# ProPrj_Loongson_Aquarii_v1_9.net
KiCad netlist of a schematic drawn in EasyEDA Pro
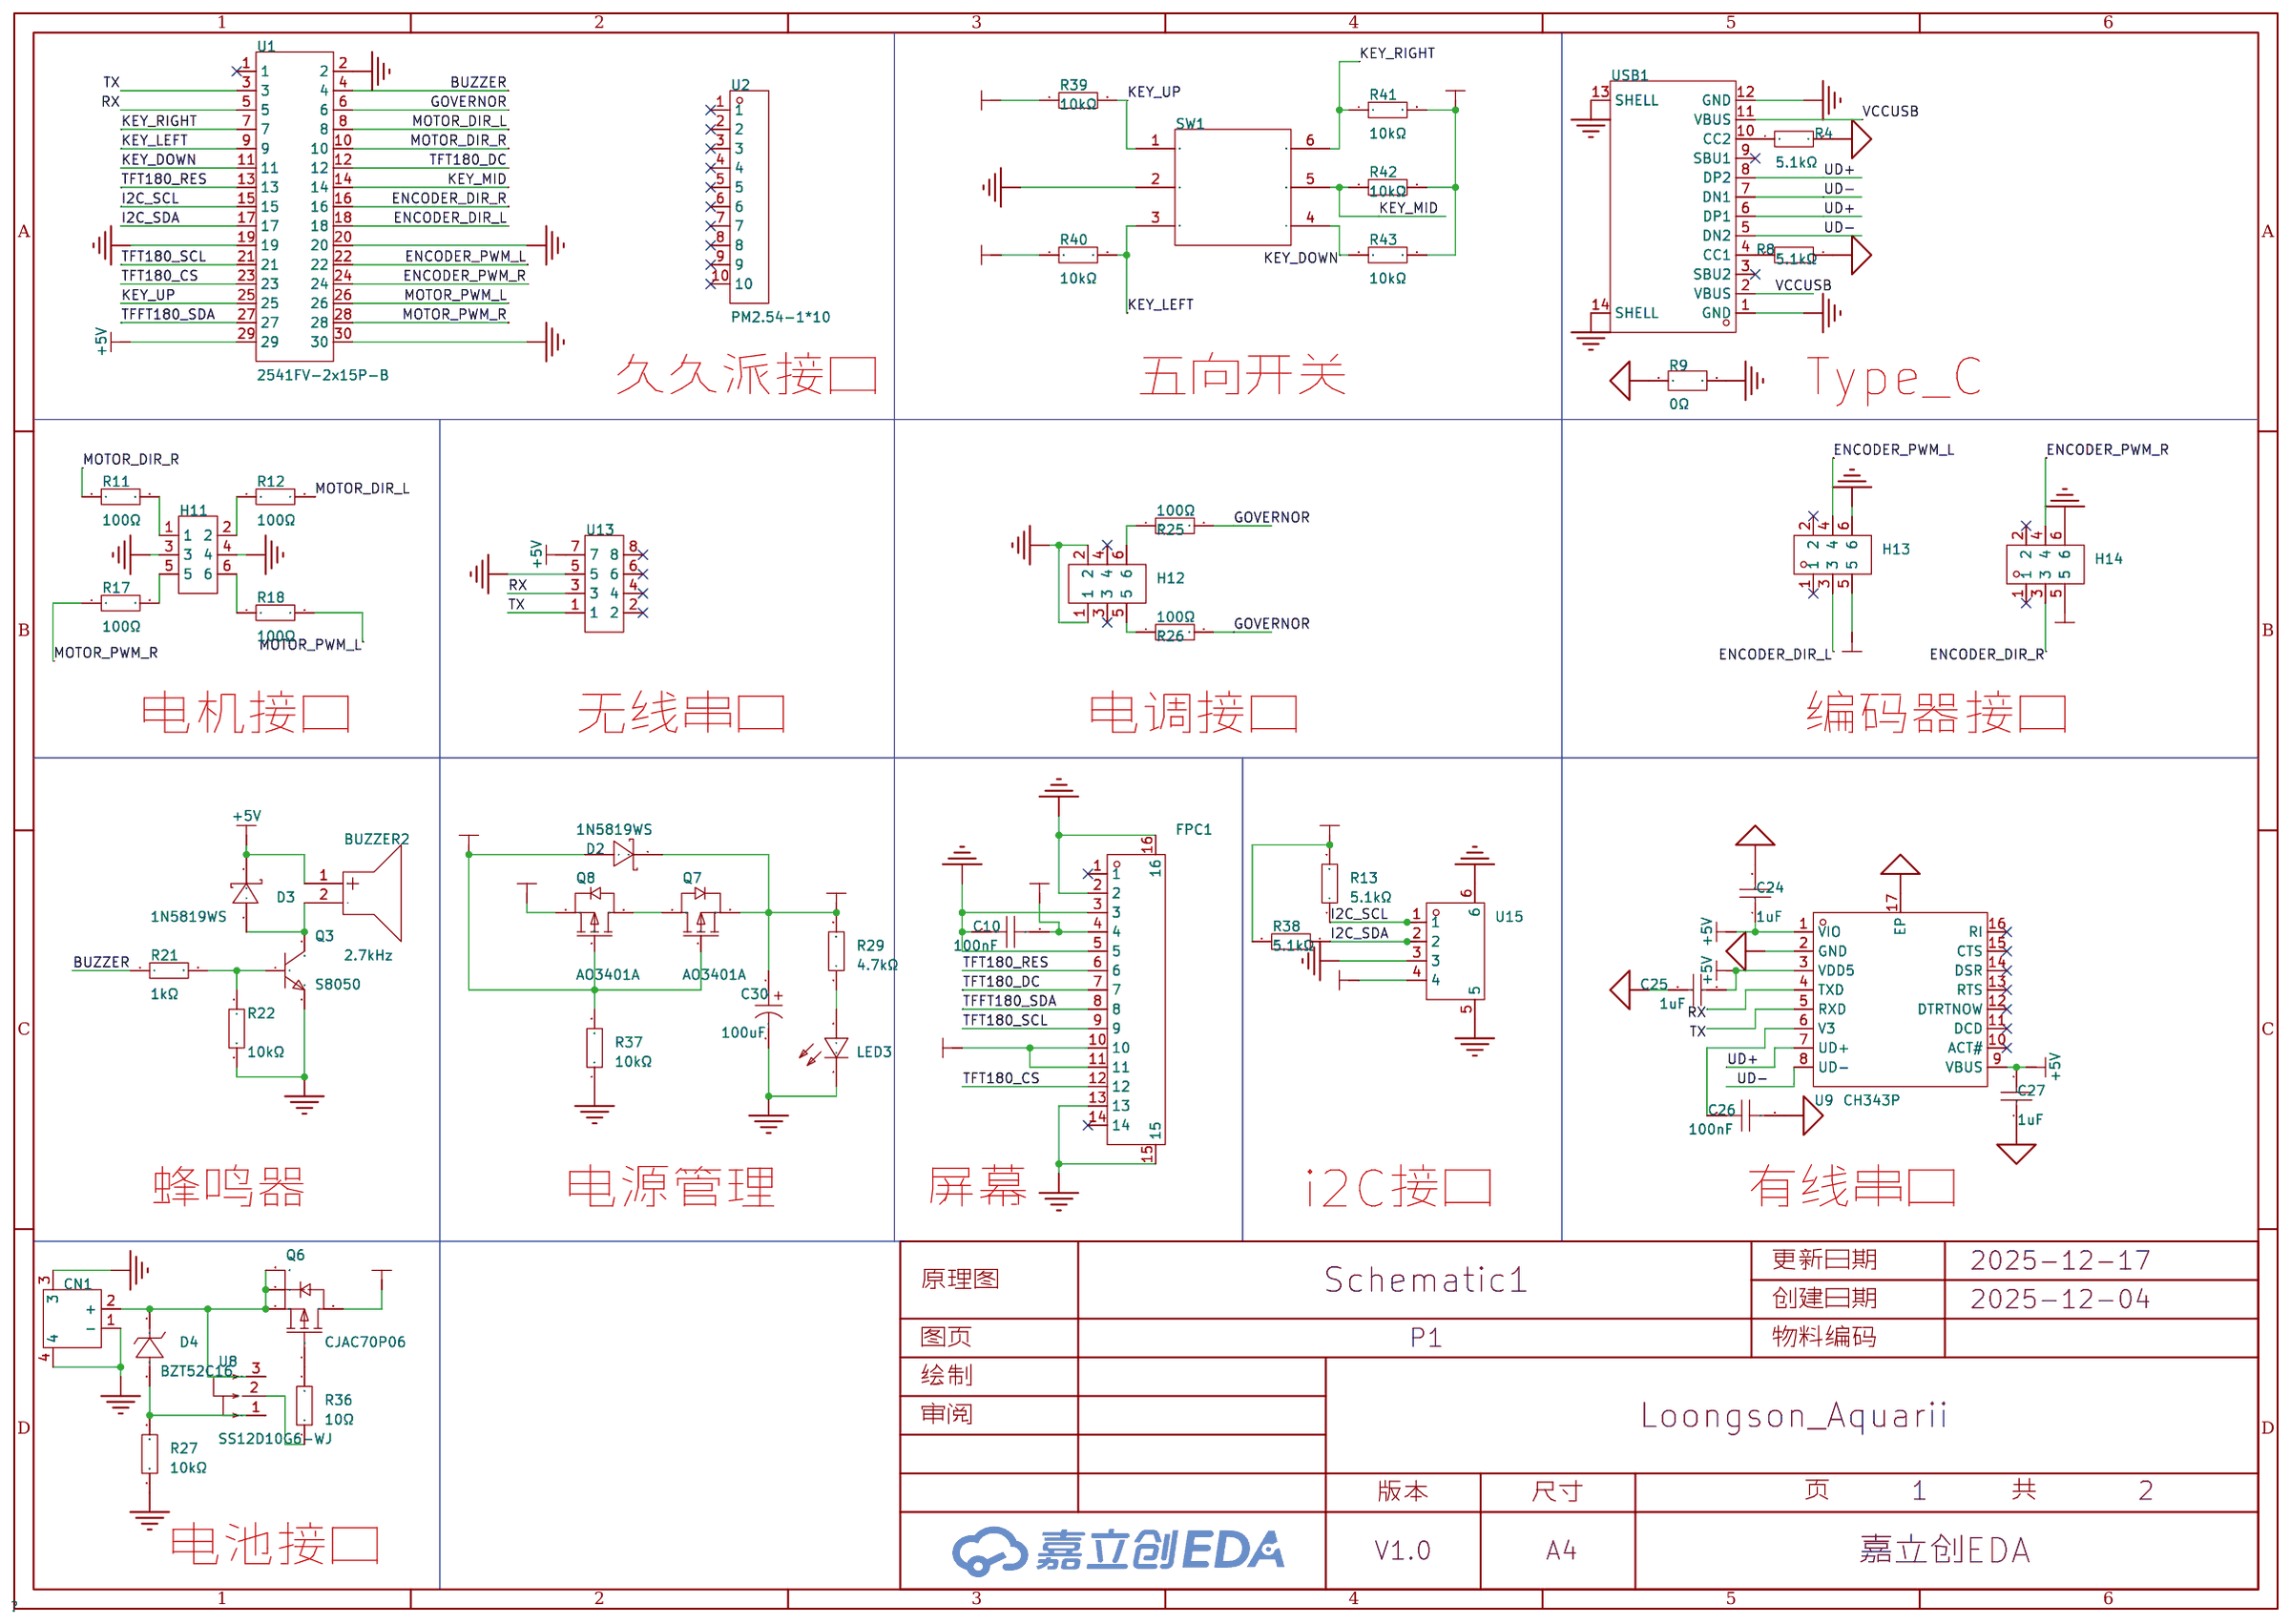
[diagram p0: P1]
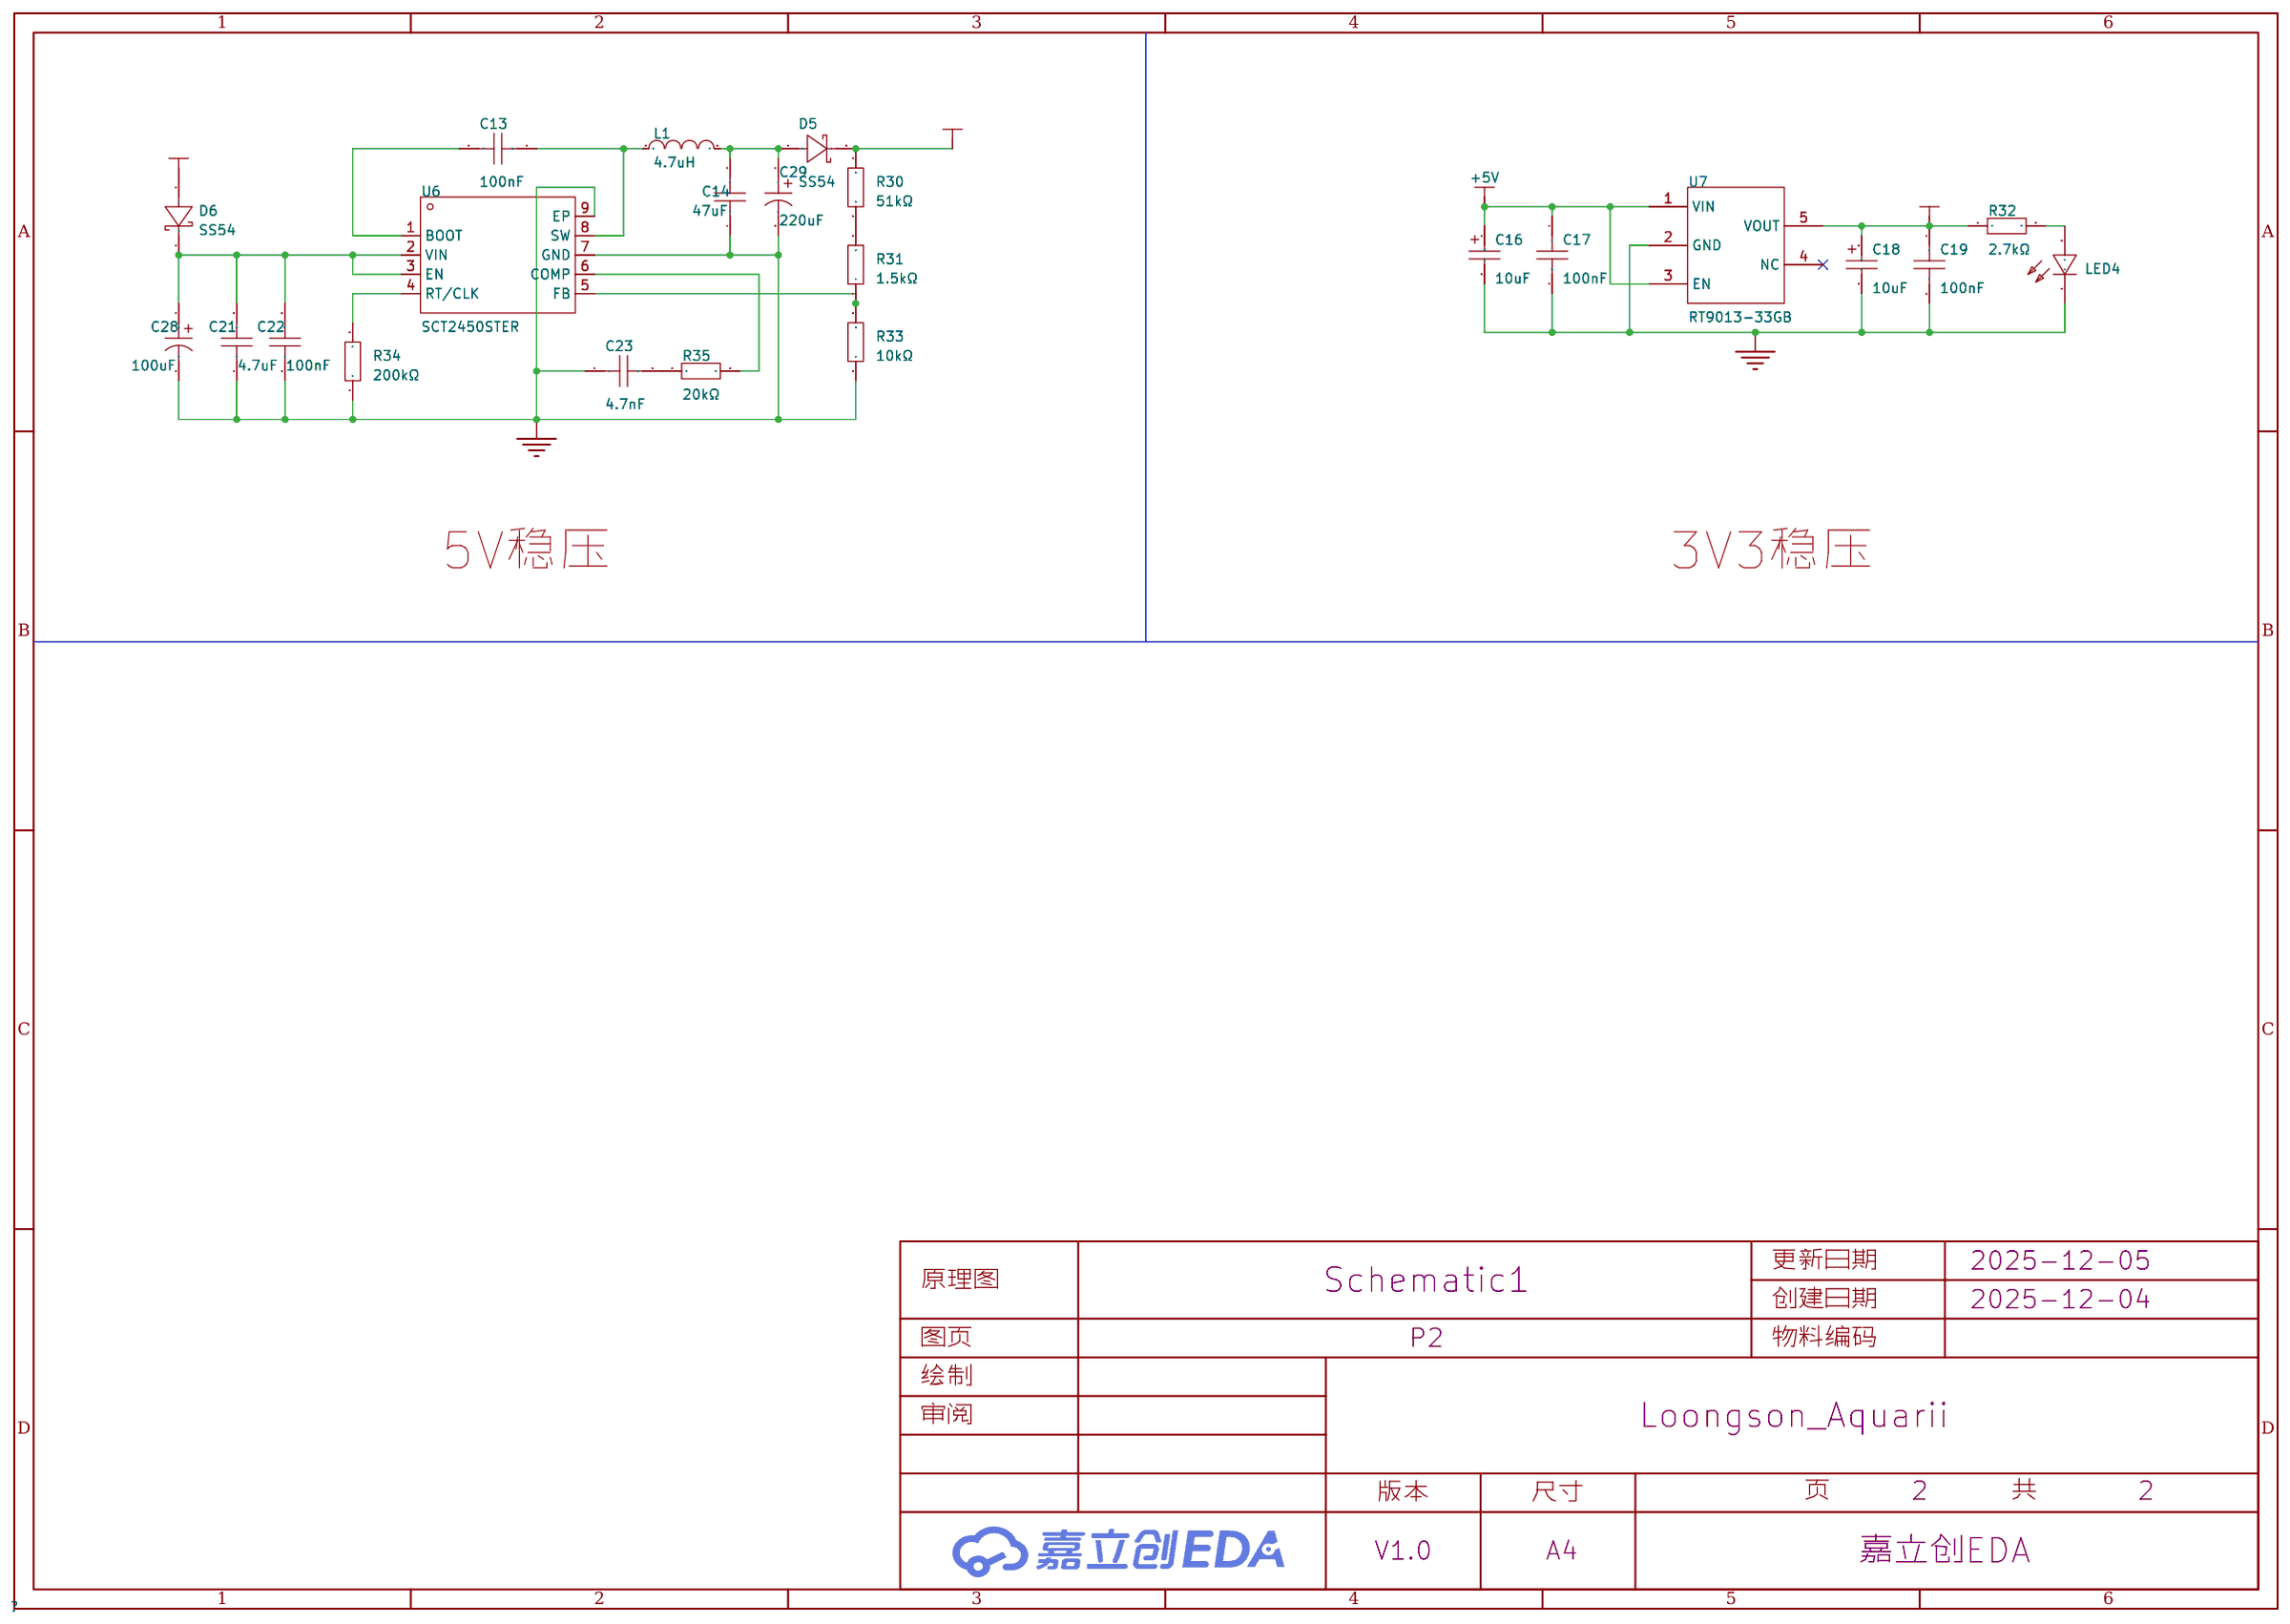
[diagram p1: P2]

(export (version "E")
  (design (tool "Eeschema 10.0.6"))
  (components
    (comp (ref "BUZZER2")
      (value "2.7kHz")
      (footprint "easyedapro:BUZ-SMD_GSC9032RB")
      (description "驱动方式:无源(外部驱动);构造类型:电磁式;额定电压:3.6V;频率:2.7kHz;声压(SPL):85dB;")
      (fields
        (field (name "Manufacturer Part") "GSC9032RB-16R2700")
        (field (name "Manufacturer") "INGHAi(赢海)")
      )
      (libsource (lib "easyedapro") (part "GSC9032RB-16R2700"))
    )
    (comp (ref "C10")
      (value "100nF")
      (footprint "easyedapro:C0603")
      (description "容值:100nF;精度:±10%;额定电压:50V;材质(温度系数):X7R;")
      (fields
        (field (name "Manufacturer Part") "CGA0603X7R104K500JT")
        (field (name "Manufacturer") "HRE(芯声)")
      )
      (libsource (lib "easyedapro") (part "CGA0603X7R104K500JT"))
    )
    (comp (ref "C24")
      (value "1uF")
      (footprint "easyedapro:C0805")
      (description "容值:1uF;精度:±10%;额定电压:50V;温度系数:X7R;")
      (fields
        (field (name "Manufacturer Part") "CL21B105KBFNNNE")
        (field (name "Manufacturer") "SAMSUNG(三星)")
      )
      (libsource (lib "easyedapro") (part "CL21B105KBFNNNE"))
    )
    (comp (ref "C25")
      (value "1uF")
      (footprint "easyedapro:C0805")
      (description "容值:1uF;精度:±10%;额定电压:50V;温度系数:X7R;")
      (fields
        (field (name "Manufacturer Part") "CL21B105KBFNNNE")
        (field (name "Manufacturer") "SAMSUNG(三星)")
      )
      (libsource (lib "easyedapro") (part "CL21B105KBFNNNE"))
    )
    (comp (ref "C26")
      (value "100nF")
      (footprint "easyedapro:C0603")
      (description "容值:100nF;精度:±10%;额定电压:50V;材质(温度系数):X7R;")
      (fields
        (field (name "Manufacturer Part") "CGA0603X7R104K500JT")
        (field (name "Manufacturer") "HRE(芯声)")
      )
      (libsource (lib "easyedapro") (part "CGA0603X7R104K500JT"))
    )
    (comp (ref "C27")
      (value "1uF")
      (footprint "easyedapro:C0805")
      (description "容值:1uF;精度:±10%;额定电压:50V;温度系数:X7R;")
      (fields
        (field (name "Manufacturer Part") "CL21B105KBFNNNE")
        (field (name "Manufacturer") "SAMSUNG(三星)")
      )
      (libsource (lib "easyedapro") (part "CL21B105KBFNNNE"))
    )
    (comp (ref "C30")
      (value "100uF")
      (footprint "easyedapro:CAP-SMD_BD6.3-L6.6-W6.6-FD-1")
      (description "容值:100uF;精度:±20%;额定电压:25V;纹波电流:72mA@120Hz;")
      (fields (field (name "Manufacturer Part") "JVJ25V100M6x5") (field (name "Manufacturer") "JIERR(捷而瑞)"))
      (libsource (lib "easyedapro") (part "JVJ25V100M6X5"))
    )
    (comp (ref "CN1")
      (value "XT30PW-M30.G.Y")
      (footprint "easyedapro:CONN-TH_XT30PW-M")
      (description "类别:-;类型1:-;")
      (fields (field (name "Manufacturer") "AMASS(艾迈斯)"))
      (libsource (lib "easyedapro") (part "XT30PW-M"))
    )
    (comp (ref "D2")
      (value "1N5819WS")
      (footprint "easyedapro:SOD-323_L1.8-W1.3-LS2.5-RD")
      (description "正向压降(Vf):600mV@1A;直流反向耐压(Vr):40V;整流电流:1A;")
      (fields (field (name "Manufacturer") "Hottech(合科泰)"))
      (libsource (lib "easyedapro") (part "1N5819WS"))
    )
    (comp (ref "D3")
      (value "1N5819WS")
      (footprint "easyedapro:SOD-323_L1.8-W1.3-LS2.5-RD")
      (description "正向压降(Vf):600mV@1A;直流反向耐压(Vr):40V;整流电流:1A;")
      (fields (field (name "Manufacturer") "Hottech(合科泰)"))
      (libsource (lib "easyedapro") (part "1N5819WS"))
    )
    (comp (ref "D4")
      (value "BZT52C16")
      (footprint "easyedapro:SOD-123_L2.7-W1.6-LS3.7-RD")
      (description "二极管配置:独立式;稳压值(标称值):16V;稳压值(范围):15.2V~16.8V;耗散功率(Pd):500mW;")
      (fields (field (name "Manufacturer") "宏嘉诚"))
      (libsource (lib "easyedapro") (part "BZT52C16_C19077413"))
    )
    (comp (ref "FPC1")
      (value "HC-FPC-05-09-14RLTAG")
      (footprint "easyedapro:FPC-SMD_14P-P0.50_HC-FPC-05-09-14RLTAG")
      (description "锁定特性:翻盖式;触点类型:双侧触点/上下接;触点数量:14P;间距:0.5mm;安装方式:卧贴;工作温度:-55°C~+85°C;")
      (fields (field (name "Manufacturer") "HCTL(华灿天禄)"))
      (libsource (lib "easyedapro") (part "HC-FPC-05-09-14RLTAG"))
    )
    (comp (ref "H11")
      (value "HX PZ2.54-2x3P TP")
      (footprint "easyedapro:HDR-SMD_6P-P2.54-V-M-R2-C3-LS7.2_M20-8760342")
      (fields (field (name "Manufacturer") "hanxia(韩下)"))
      (libsource (lib "easyedapro") (part "HX PZ2.54-2X3P TP"))
    )
    (comp (ref "H12")
      (value "HX PZ2.54-2x3P TP")
      (footprint "easyedapro:HDR-SMD_6P-P2.54-V-M-R2-C3-LS7.2_M20-8760342")
      (fields (field (name "Manufacturer") "hanxia(韩下)"))
      (libsource (lib "easyedapro") (part "HX PZ2.54-2X3P TP"))
    )
    (comp (ref "H13")
      (value "PZ254V-12-6P")
      (footprint "easyedapro:HDR-TH_6P-P2.54-V-M-R2-C3-S2.54")
      (fields (field (name "Manufacturer") "XFCN(兴飞)"))
      (libsource (lib "easyedapro") (part "PZ254V-12-6P"))
    )
    (comp (ref "H14")
      (value "PZ254V-12-6P")
      (footprint "easyedapro:HDR-TH_6P-P2.54-V-M-R2-C3-S2.54")
      (fields (field (name "Manufacturer") "XFCN(兴飞)"))
      (libsource (lib "easyedapro") (part "PZ254V-12-6P"))
    )
    (comp (ref "LED3")
      (value "NCD0603R1")
      (footprint "easyedapro:LED0603-RD_RED")
      (fields (field (name "Manufacturer") "国星光电"))
      (libsource (lib "easyedapro") (part "FC-DA1608HRK-620D"))
    )
    (comp (ref "Q3")
      (value "S8050")
      (footprint "easyedapro:SOT-23-3_L2.9-W1.6-P1.90-LS2.8-BR")
      (description "晶体管类型:NPN;集电极电流(Ic):500mA;集射极击穿电压(Vceo):25V;功率(Pd):300mW;")
      (fields (field (name "Manufacturer") "Hottech(合科泰)"))
      (libsource (lib "easyedapro") (part "S8050_C181158"))
    )
    (comp (ref "Q6")
      (value "CJAC70P06")
      (footprint "easyedapro:TDSON-8_L5.9-W5.2-P1.27-BL")
      (fields (field (name "Manufacturer") "CJ(江苏长电/长晶)"))
      (libsource (lib "easyedapro") (part "CJAC70P06"))
    )
    (comp (ref "Q7")
      (value "AO3401A")
      (footprint "easyedapro:SOT-23_L2.9-W1.3-P1.90-LS2.4-BR")
      (fields (field (name "Manufacturer") "UMW(友台半导体)"))
      (libsource (lib "easyedapro") (part "AO3401A_C347476"))
    )
    (comp (ref "Q8")
      (value "AO3401A")
      (footprint "easyedapro:SOT-23_L2.9-W1.3-P1.90-LS2.4-BR")
      (fields (field (name "Manufacturer") "UMW(友台半导体)"))
      (libsource (lib "easyedapro") (part "AO3401A_C347476"))
    )
    (comp (ref "R4")
      (value "5.1kΩ")
      (footprint "easyedapro:R0603")
      (description "电阻类型:厚膜电阻;阻值:5.1kΩ;精度:±1%;功率:100mW;最大工作电压:75V;温度系数:±100ppm/°C;")
      (fields
        (field (name "Manufacturer Part") "0603WAF5101T5E")
        (field (name "Manufacturer") "UNI-ROYAL(厚声)")
      )
      (libsource (lib "easyedapro") (part "0603WAF5101T5E"))
    )
    (comp (ref "R8")
      (value "5.1kΩ")
      (footprint "easyedapro:R0603")
      (description "电阻类型:厚膜电阻;阻值:5.1kΩ;精度:±1%;功率:100mW;最大工作电压:75V;温度系数:±100ppm/°C;")
      (fields
        (field (name "Manufacturer Part") "0603WAF5101T5E")
        (field (name "Manufacturer") "UNI-ROYAL(厚声)")
      )
      (libsource (lib "easyedapro") (part "0603WAF5101T5E"))
    )
    (comp (ref "R9")
      (value "0Ω")
      (footprint "easyedapro:R1206")
      (description "电阻类型:厚膜电阻;阻值:0Ω;精度:±5%;功率:250mW;最大工作电压:200V;")
      (fields (field (name "Manufacturer Part") "FRC1206P000 TS") (field (name "Manufacturer") "FOJAN(富捷)"))
      (libsource (lib "easyedapro") (part "FRC1206P000 TS"))
    )
    (comp (ref "R11")
      (value "100Ω")
      (footprint "easyedapro:R0603")
      (description "电阻类型:厚膜电阻;阻值:100Ω;精度:±1%;功率:100mW;最大工作电压:75V;温度系数:±200ppm/°C;")
      (fields
        (field (name "Manufacturer Part") "0603WAF1000T5E")
        (field (name "Manufacturer") "UNI-ROYAL(厚声)")
      )
      (libsource (lib "easyedapro") (part "0603WAF1000T5E"))
    )
    (comp (ref "R12")
      (value "100Ω")
      (footprint "easyedapro:R0603")
      (description "电阻类型:厚膜电阻;阻值:100Ω;精度:±1%;功率:100mW;最大工作电压:75V;温度系数:±200ppm/°C;")
      (fields
        (field (name "Manufacturer Part") "0603WAF1000T5E")
        (field (name "Manufacturer") "UNI-ROYAL(厚声)")
      )
      (libsource (lib "easyedapro") (part "0603WAF1000T5E"))
    )
    (comp (ref "R13")
      (value "5.1kΩ")
      (footprint "easyedapro:R0603")
      (description "电阻类型:厚膜电阻;阻值:5.1kΩ;精度:±1%;功率:100mW;最大工作电压:75V;温度系数:±100ppm/°C;")
      (fields
        (field (name "Manufacturer Part") "0603WAF5101T5E")
        (field (name "Manufacturer") "UNI-ROYAL(厚声)")
      )
      (libsource (lib "easyedapro") (part "0603WAF5101T5E"))
    )
    (comp (ref "R17")
      (value "100Ω")
      (footprint "easyedapro:R0603")
      (description "电阻类型:厚膜电阻;阻值:100Ω;精度:±1%;功率:100mW;最大工作电压:75V;温度系数:±200ppm/°C;")
      (fields
        (field (name "Manufacturer Part") "0603WAF1000T5E")
        (field (name "Manufacturer") "UNI-ROYAL(厚声)")
      )
      (libsource (lib "easyedapro") (part "0603WAF1000T5E"))
    )
    (comp (ref "R18")
      (value "100Ω")
      (footprint "easyedapro:R0603")
      (description "电阻类型:厚膜电阻;阻值:100Ω;精度:±1%;功率:100mW;最大工作电压:75V;温度系数:±200ppm/°C;")
      (fields
        (field (name "Manufacturer Part") "0603WAF1000T5E")
        (field (name "Manufacturer") "UNI-ROYAL(厚声)")
      )
      (libsource (lib "easyedapro") (part "0603WAF1000T5E"))
    )
    (comp (ref "R21")
      (value "1kΩ")
      (footprint "easyedapro:R0603")
      (description "电阻类型:厚膜电阻;阻值:1kΩ;精度:±1%;功率:100mW;工作电压:75V;温度系数:±100ppm/°C;")
      (fields
        (field (name "Manufacturer Part") "0603WAF1001T5E")
        (field (name "Manufacturer") "UNI-ROYAL(厚声)")
      )
      (libsource (lib "easyedapro") (part "0603WAF1001T5E"))
    )
    (comp (ref "R22")
      (value "10kΩ")
      (footprint "easyedapro:R0603")
      (description "电阻类型:厚膜电阻;阻值:10kΩ;精度:±1%;功率:100mW;最大工作电压:75V;温度系数:±100ppm/°C;")
      (fields
        (field (name "Manufacturer Part") "0603WAF1002T5E")
        (field (name "Manufacturer") "UNI-ROYAL(厚声)")
      )
      (libsource (lib "easyedapro") (part "0603WAF1002T5E"))
    )
    (comp (ref "R25")
      (value "100Ω")
      (footprint "easyedapro:R0603")
      (description "电阻类型:厚膜电阻;阻值:100Ω;精度:±1%;功率:100mW;最大工作电压:75V;温度系数:±200ppm/°C;")
      (fields
        (field (name "Manufacturer Part") "0603WAF1000T5E")
        (field (name "Manufacturer") "UNI-ROYAL(厚声)")
      )
      (libsource (lib "easyedapro") (part "0603WAF1000T5E"))
    )
    (comp (ref "R26")
      (value "100Ω")
      (footprint "easyedapro:R0603")
      (description "电阻类型:厚膜电阻;阻值:100Ω;精度:±1%;功率:100mW;最大工作电压:75V;温度系数:±200ppm/°C;")
      (fields
        (field (name "Manufacturer Part") "0603WAF1000T5E")
        (field (name "Manufacturer") "UNI-ROYAL(厚声)")
      )
      (libsource (lib "easyedapro") (part "0603WAF1000T5E"))
    )
    (comp (ref "R27")
      (value "10kΩ")
      (footprint "easyedapro:R0603")
      (description "电阻类型:厚膜电阻;阻值:10kΩ;精度:±1%;功率:100mW;最大工作电压:75V;温度系数:±100ppm/°C;")
      (fields
        (field (name "Manufacturer Part") "0603WAF1002T5E")
        (field (name "Manufacturer") "UNI-ROYAL(厚声)")
      )
      (libsource (lib "easyedapro") (part "0603WAF1002T5E"))
    )
    (comp (ref "R29")
      (value "4.7kΩ")
      (footprint "easyedapro:R0603")
      (description "电阻类型:厚膜电阻;阻值:4.7kΩ;精度:±1%;功率:100mW;最大工作电压:75V;温度系数:±100ppm/°C;")
      (fields
        (field (name "Manufacturer Part") "0603WAF4701T5E")
        (field (name "Manufacturer") "UNI-ROYAL(厚声)")
      )
      (libsource (lib "easyedapro") (part "0603WAF4701T5E"))
    )
    (comp (ref "R36")
      (value "10Ω")
      (footprint "easyedapro:R0603")
      (description "电阻类型:厚膜电阻;阻值:10Ω;精度:±1%;功率:100mW;最大工作电压:75V;温度系数:±400ppm/°C;")
      (fields
        (field (name "Manufacturer Part") "0603WAF100JT5E")
        (field (name "Manufacturer") "UNI-ROYAL(厚声)")
      )
      (libsource (lib "easyedapro") (part "0603WAF100JT5E"))
    )
    (comp (ref "R37")
      (value "10kΩ")
      (footprint "easyedapro:R0603")
      (description "电阻类型:厚膜电阻;阻值:10kΩ;精度:±1%;功率:100mW;最大工作电压:75V;温度系数:±100ppm/°C;")
      (fields
        (field (name "Manufacturer Part") "0603WAF1002T5E")
        (field (name "Manufacturer") "UNI-ROYAL(厚声)")
      )
      (libsource (lib "easyedapro") (part "0603WAF1002T5E"))
    )
    (comp (ref "R38")
      (value "5.1kΩ")
      (footprint "easyedapro:R0603")
      (description "电阻类型:厚膜电阻;阻值:5.1kΩ;精度:±1%;功率:100mW;最大工作电压:75V;温度系数:±100ppm/°C;")
      (fields
        (field (name "Manufacturer Part") "0603WAF5101T5E")
        (field (name "Manufacturer") "UNI-ROYAL(厚声)")
      )
      (libsource (lib "easyedapro") (part "0603WAF5101T5E"))
    )
    (comp (ref "R39")
      (value "10kΩ")
      (footprint "easyedapro:R0603")
      (description "电阻类型:厚膜电阻;阻值:10kΩ;精度:±1%;功率:100mW;最大工作电压:75V;温度系数:±100ppm/°C;")
      (fields
        (field (name "Manufacturer Part") "0603WAF1002T5E")
        (field (name "Manufacturer") "UNI-ROYAL(厚声)")
      )
      (libsource (lib "easyedapro") (part "0603WAF1002T5E"))
    )
    (comp (ref "R40")
      (value "10kΩ")
      (footprint "easyedapro:R0603")
      (description "电阻类型:厚膜电阻;阻值:10kΩ;精度:±1%;功率:100mW;最大工作电压:75V;温度系数:±100ppm/°C;")
      (fields
        (field (name "Manufacturer Part") "0603WAF1002T5E")
        (field (name "Manufacturer") "UNI-ROYAL(厚声)")
      )
      (libsource (lib "easyedapro") (part "0603WAF1002T5E"))
    )
    (comp (ref "R41")
      (value "10kΩ")
      (footprint "easyedapro:R0603")
      (description "电阻类型:厚膜电阻;阻值:10kΩ;精度:±1%;功率:100mW;最大工作电压:75V;温度系数:±100ppm/°C;")
      (fields
        (field (name "Manufacturer Part") "0603WAF1002T5E")
        (field (name "Manufacturer") "UNI-ROYAL(厚声)")
      )
      (libsource (lib "easyedapro") (part "0603WAF1002T5E"))
    )
    (comp (ref "R42")
      (value "10kΩ")
      (footprint "easyedapro:R0603")
      (description "电阻类型:厚膜电阻;阻值:10kΩ;精度:±1%;功率:100mW;最大工作电压:75V;温度系数:±100ppm/°C;")
      (fields
        (field (name "Manufacturer Part") "0603WAF1002T5E")
        (field (name "Manufacturer") "UNI-ROYAL(厚声)")
      )
      (libsource (lib "easyedapro") (part "0603WAF1002T5E"))
    )
    (comp (ref "R43")
      (value "10kΩ")
      (footprint "easyedapro:R0603")
      (description "电阻类型:厚膜电阻;阻值:10kΩ;精度:±1%;功率:100mW;最大工作电压:75V;温度系数:±100ppm/°C;")
      (fields
        (field (name "Manufacturer Part") "0603WAF1002T5E")
        (field (name "Manufacturer") "UNI-ROYAL(厚声)")
      )
      (libsource (lib "easyedapro") (part "0603WAF1002T5E"))
    )
    (comp (ref "SW1")
      (value "7*7*5-6P-L WX")
      (footprint "easyedapro:SW-SMD_8P-L7.0-W7.0-P1.40-LS7.4-TL")
      (fields (field (name "Manufacturer") "SHOU HAN(首韩)"))
      (libsource (lib "easyedapro") (part "7*7*5-6P-L WX"))
    )
    (comp (ref "U1")
      (value "2541FV-2x15P-B")
      (footprint "easyedapro:HDR-TH_30P-P2.54-V-F-R2-C15-S2.54")
      (fields (field (name "Manufacturer") "HanElectricity(瀚源)"))
      (libsource (lib "easyedapro") (part "2541FV-2X15P-B"))
    )
    (comp (ref "U2")
      (value "PM2.54-1*10")
      (footprint "easyedapro:HDR-TH_10P-P2.54-V-F")
      (fields (field (name "Manufacturer") "ZHOURI(洲日)"))
      (libsource (lib "easyedapro") (part "PM2.54-1*10"))
    )
    (comp (ref "U8")
      (value "SS12D10G6-WJ")
      (footprint "easyedapro:SW-TH_3P-P4.80_HX-SS12D10G6-WJ")
      (description "电路结构:单刀双掷;安装方式:弯插;开关颜色:黑色;额定电流:2A;额定电压:125V;工作寿命:3千次;")
      (fields (field (name "Manufacturer") "SHOU HAN(首韩)"))
      (libsource (lib "easyedapro") (part "SS12D10G6-WJ"))
    )
    (comp (ref "U9")
      (value "CH343P")
      (footprint "easyedapro:TQFN-16_L3.0-W3.0-P0.50-BL-EP1.7")
      (description "应用功能:USB转UART;USB协议版本:USB 2.0;通道数:-;数据速率:6Mbps;")
      (fields (field (name "Manufacturer") "WCH(南京沁恒)"))
      (libsource (lib "easyedapro") (part "CH343P"))
    )
    (comp (ref "U13")
      (value "5BME8-08872-204-W0")
      (footprint "easyedapro:CONN-SMD_5BME8-08872-204-W0")
      (fields (field (name "Manufacturer") "SAMZO(三佐)"))
      (libsource (lib "easyedapro") (part "5BME8-08872-204-W0"))
    )
    (comp (ref "U15")
      (value "2.54-4PWTDK")
      (footprint "easyedapro:CONN-SMD_4P-P2.50_SHOU_2.54-4PWTDK")
      (fields (field (name "Manufacturer") "SHOU HAN(首韩)"))
      (libsource (lib "easyedapro") (part "2.54-4PWTDK"))
    )
    (comp (ref "USB1")
      (value "TYPE-C 16PIN 2MD(073)")
      (footprint "easyedapro:USB-C-SMD_TYPE-C-6PIN-2MD-073")
      (description "连接器类型:Type-C;标准:USB 3.1;公母:母;安装方式:卧贴;触点数量:16P;端口数量:1;额定电流 - 电源:5A;工作温度范围:-25°C~+85°C;")
      (fields (field (name "Manufacturer") "SHOU HAN(首韩)"))
      (libsource (lib "easyedapro") (part "TYPE-C 16PIN 2MD(073)"))
    )
    (comp (ref "C13")
      (value "100nF")
      (footprint "easyedapro:C0603")
      (description "容值:100nF;精度:±10%;额定电压:50V;材质(温度系数):X7R;")
      (fields
        (field (name "Manufacturer Part") "CGA0603X7R104K500JT")
        (field (name "Manufacturer") "HRE(芯声)")
      )
      (libsource (lib "easyedapro") (part "CGA0603X7R104K500JT"))
    )
    (comp (ref "C14")
      (value "47uF")
      (footprint "easyedapro:C1206")
      (description "容值:47uF;精度:±20%;额定电压:25V;材质(温度系数):X5R;")
      (fields
        (field (name "Manufacturer Part") "CGA1206X5R476M250NT")
        (field (name "Manufacturer") "HRE(芯声)")
      )
      (libsource (lib "easyedapro") (part "CGA1206X5R476M250NT"))
    )
    (comp (ref "C16")
      (value "10uF")
      (footprint "easyedapro:CAP-SMD_L3.2-W1.6-RD-C7171")
      (description "容值:10uF;精度:±10%;额定电压:16V;等效串联电阻:3Ω@100kHz;")
      (fields (field (name "Manufacturer Part") "TAJA106K016RNJ") (field (name "Manufacturer") "Kyocera AVX"))
      (libsource (lib "easyedapro") (part "TAJA106K016RNJ"))
    )
    (comp (ref "C17")
      (value "100nF")
      (footprint "easyedapro:C0603")
      (description "容值:100nF;精度:±10%;额定电压:50V;材质(温度系数):X7R;")
      (fields
        (field (name "Manufacturer Part") "CGA0603X7R104K500JT")
        (field (name "Manufacturer") "HRE(芯声)")
      )
      (libsource (lib "easyedapro") (part "CGA0603X7R104K500JT"))
    )
    (comp (ref "C18")
      (value "10uF")
      (footprint "easyedapro:CAP-SMD_L3.2-W1.6-RD-C7171")
      (description "容值:10uF;精度:±10%;额定电压:16V;等效串联电阻:3Ω@100kHz;")
      (fields (field (name "Manufacturer Part") "TAJA106K016RNJ") (field (name "Manufacturer") "Kyocera AVX"))
      (libsource (lib "easyedapro") (part "TAJA106K016RNJ"))
    )
    (comp (ref "C19")
      (value "100nF")
      (footprint "easyedapro:C0603")
      (description "容值:100nF;精度:±10%;额定电压:50V;材质(温度系数):X7R;")
      (fields
        (field (name "Manufacturer Part") "CGA0603X7R104K500JT")
        (field (name "Manufacturer") "HRE(芯声)")
      )
      (libsource (lib "easyedapro") (part "CGA0603X7R104K500JT"))
    )
    (comp (ref "C21")
      (value "4.7uF")
      (footprint "easyedapro:C1206")
      (description "容值:4.7uF;精度:±10%;额定电压:35V;材质(温度系数):X5R;")
      (fields
        (field (name "Manufacturer Part") "CGA1206X5R475K350NT")
        (field (name "Manufacturer") "HRE(芯声)")
      )
      (libsource (lib "easyedapro") (part "CGA1206X5R475K350NT"))
    )
    (comp (ref "C22")
      (value "100nF")
      (footprint "easyedapro:C0603")
      (description "容值:100nF;精度:±10%;额定电压:50V;材质(温度系数):X7R;")
      (fields
        (field (name "Manufacturer Part") "CGA0603X7R104K500JT")
        (field (name "Manufacturer") "HRE(芯声)")
      )
      (libsource (lib "easyedapro") (part "CGA0603X7R104K500JT"))
    )
    (comp (ref "C23")
      (value "4.7nF")
      (footprint "easyedapro:C0603")
      (description "容值:4.7nF;精度:±10%;额定电压:50V;材质(温度系数):X7R;")
      (fields
        (field (name "Manufacturer Part") "CGA0603X7R472K500JT")
        (field (name "Manufacturer") "HRE(芯声)")
      )
      (libsource (lib "easyedapro") (part "CGA0603X7R472K500JT"))
    )
    (comp (ref "C28")
      (value "100uF")
      (footprint "easyedapro:CAP-SMD_BD6.3-L6.6-W6.6-FD-1")
      (description "容值:100uF;精度:±20%;额定电压:25V;纹波电流:72mA@120Hz;")
      (fields (field (name "Manufacturer Part") "JVJ25V100M6x5") (field (name "Manufacturer") "JIERR(捷而瑞)"))
      (libsource (lib "easyedapro") (part "JVJ25V100M6X5"))
    )
    (comp (ref "C29")
      (value "220uF")
      (footprint "easyedapro:CAP-SMD_BD6.3-L6.6-W6.6-LS7.3-FD-H7.7")
      (description "容值:220uF;精度:±20%;额定电压:25V;纹波电流:120mA@120Hz;")
      (fields (field (name "Manufacturer Part") "JVJ25V220M6x8") (field (name "Manufacturer") "JIERR(捷而瑞)"))
      (libsource (lib "easyedapro") (part "JVJ25V220M6X8"))
    )
    (comp (ref "D5")
      (value "SS54")
      (footprint "easyedapro:SMA_L4.3-W2.6-LS5.0-FD")
      (description "二极管配置:独立式;正向压降(Vf):550mV@5.0A;直流反向耐压(Vr):40V;整流电流:5A;")
      (fields (field (name "Manufacturer") "宏迦橙"))
      (libsource (lib "easyedapro") (part "SS54_C7420369"))
    )
    (comp (ref "D6")
      (value "SS54")
      (footprint "easyedapro:SMA_L4.3-W2.6-LS5.0-FD")
      (description "二极管配置:独立式;正向压降(Vf):550mV@5.0A;直流反向耐压(Vr):40V;整流电流:5A;")
      (fields (field (name "Manufacturer") "宏迦橙"))
      (libsource (lib "easyedapro") (part "SS54_C7420369"))
    )
    (comp (ref "L1")
      (value "4.7uH")
      (footprint "easyedapro:IND-SMD_L5.4-W5.2_FXL0530")
      (description "电感值:4.7uH;精度:±20%;额定电流:4.5A;饱和电流(Isat):5A;类型:一体成型电感;")
      (fields (field (name "Manufacturer Part") "FXL0530-4R7-M") (field (name "Manufacturer") "cjiang(长江微电)"))
      (libsource (lib "easyedapro") (part "FXL0530-4R7-M"))
    )
    (comp (ref "LED4")
      (value "NCD0603R1")
      (footprint "easyedapro:LED0603-RD_RED")
      (fields (field (name "Manufacturer") "国星光电"))
      (libsource (lib "easyedapro") (part "FC-DA1608HRK-620D"))
    )
    (comp (ref "R30")
      (value "51kΩ")
      (footprint "easyedapro:R0603")
      (description "电阻类型:厚膜电阻;阻值:51kΩ;精度:±1%;功率:100mW;最大工作电压:75V;温度系数:±100ppm/°C;")
      (fields
        (field (name "Manufacturer Part") "0603WAF5102T5E")
        (field (name "Manufacturer") "UNI-ROYAL(厚声)")
      )
      (libsource (lib "easyedapro") (part "0603WAF5102T5E"))
    )
    (comp (ref "R31")
      (value "1.5kΩ")
      (footprint "easyedapro:R0603")
      (description "电阻类型:厚膜电阻;阻值:1.5kΩ;精度:±1%;功率:100mW;最大工作电压:75V;温度系数:±100ppm/°C;")
      (fields
        (field (name "Manufacturer Part") "0603WAF1501T5E")
        (field (name "Manufacturer") "UNI-ROYAL(厚声)")
      )
      (libsource (lib "easyedapro") (part "0603WAF1501T5E"))
    )
    (comp (ref "R32")
      (value "2.7kΩ")
      (footprint "easyedapro:R0603")
      (description "电阻类型:厚膜电阻;阻值:2.7kΩ;精度:±1%;功率:100mW;最大工作电压:75V;温度系数:±100ppm/°C;")
      (fields
        (field (name "Manufacturer Part") "0603WAF2701T5E")
        (field (name "Manufacturer") "UNI-ROYAL(厚声)")
      )
      (libsource (lib "easyedapro") (part "0603WAF2701T5E"))
    )
    (comp (ref "R33")
      (value "10kΩ")
      (footprint "easyedapro:R0603")
      (description "电阻类型:厚膜电阻;阻值:10kΩ;精度:±1%;功率:100mW;最大工作电压:75V;温度系数:±100ppm/°C;")
      (fields
        (field (name "Manufacturer Part") "0603WAF1002T5E")
        (field (name "Manufacturer") "UNI-ROYAL(厚声)")
      )
      (libsource (lib "easyedapro") (part "0603WAF1002T5E"))
    )
    (comp (ref "R34")
      (value "200kΩ")
      (footprint "easyedapro:R0603")
      (description "电阻类型:厚膜电阻;阻值:200kΩ;精度:±1%;功率:100mW;最大工作电压:75V;温度系数:±100ppm/°C;")
      (fields
        (field (name "Manufacturer Part") "0603WAF2003T5E")
        (field (name "Manufacturer") "UNI-ROYAL(厚声)")
      )
      (libsource (lib "easyedapro") (part "0603WAF2003T5E"))
    )
    (comp (ref "R35")
      (value "20kΩ")
      (footprint "easyedapro:R0603")
      (description "电阻类型:厚膜电阻;阻值:20kΩ;精度:±1%;功率:100mW;最大工作电压:75V;温度系数:±100ppm/°C;")
      (fields
        (field (name "Manufacturer Part") "0603WAF2002T5E")
        (field (name "Manufacturer") "UNI-ROYAL(厚声)")
      )
      (libsource (lib "easyedapro") (part "0603WAF2002T5E"))
    )
    (comp (ref "U6")
      (value "SCT2450STER")
      (footprint "easyedapro:ESOP-8_L4.9-W3.9-P1.27-LS6.0-BL-EP")
      (description "功能类型:降压型;工作电压:3.8V~36V;输出电流:5A;")
      (fields (field (name "Manufacturer") "SCT(芯洲科技)"))
      (libsource (lib "easyedapro") (part "SCT2450STER"))
    )
    (comp (ref "U7")
      (value "RT9013-33GB")
      (footprint "easyedapro:SOT-23-5_L3.0-W1.7-P0.95-LS2.8-BL")
      (description "输出类型:固定;最大输入电压:5.5V;输出电压:3.3V;输出电流:500mA;电源纹波抑制比(PSRR):50dB@(10kHz);输出极性:正极;")
      (fields (field (name "Manufacturer") "RICHTEK(立锜)"))
      (libsource (lib "easyedapro") (part "RT9013-33GB"))
    )
  )
  (nets
    (net (code "1") (name "+5V") (class "Default")
      (node (ref "BUZZER2") (pin "1") (pinfunction "+_1") (pintype "unspecified"))
      (node (ref "C16") (pin "1") (pinfunction "1_1") (pintype "input"))
      (node (ref "C17") (pin "1") (pinfunction "1_1") (pintype "unspecified"))
      (node (ref "C24") (pin "1") (pinfunction "1_1") (pintype "input"))
      (node (ref "C25") (pin "1") (pinfunction "1_1") (pintype "input"))
      (node (ref "C27") (pin "2") (pinfunction "2_2") (pintype "input"))
      (node (ref "C30") (pin "1") (pinfunction "1_1") (pintype "input"))
      (node (ref "D2") (pin "1") (pinfunction "K_1") (pintype "unspecified"))
      (node (ref "D3") (pin "1") (pinfunction "K_1") (pintype "unspecified"))
      (node (ref "Q7") (pin "2") (pinfunction "S_2") (pintype "unspecified"))
      (node (ref "R29") (pin "2") (pinfunction "2_2") (pintype "input"))
      (node (ref "U1") (pin "29") (pinfunction "29_29") (pintype "unspecified"))
      (node (ref "U13") (pin "7") (pinfunction "7_7") (pintype "unspecified"))
      (node (ref "U7") (pin "1") (pinfunction "VIN_1") (pintype "unspecified"))
      (node (ref "U7") (pin "3") (pinfunction "EN_3") (pintype "unspecified"))
      (node (ref "U9") (pin "1") (pinfunction "VIO_1") (pintype "unspecified"))
      (node (ref "U9") (pin "3") (pinfunction "VDD5_3") (pintype "unspecified"))
      (node (ref "U9") (pin "9") (pinfunction "VBUS_9") (pintype "unspecified"))
    )
    (net (code "2") (name "3V3") (class "Default")
      (node (ref "C10") (pin "2") (pinfunction "2_2") (pintype "unspecified"))
      (node (ref "C18") (pin "1") (pinfunction "1_1") (pintype "input"))
      (node (ref "C19") (pin "1") (pinfunction "1_1") (pintype "unspecified"))
      (node (ref "FPC1") (pin "10") (pinfunction "10_10") (pintype "unspecified"))
      (node (ref "FPC1") (pin "11") (pinfunction "11_11") (pintype "unspecified"))
      (node (ref "FPC1") (pin "4") (pinfunction "4_4") (pintype "unspecified"))
      (node (ref "H13") (pin "5") (pinfunction "5_5") (pintype "unspecified"))
      (node (ref "H14") (pin "5") (pinfunction "5_5") (pintype "unspecified"))
      (node (ref "R13") (pin "2") (pinfunction "2_2") (pintype "input"))
      (node (ref "R32") (pin "1") (pinfunction "1_1") (pintype "input"))
      (node (ref "R38") (pin "2") (pinfunction "2_2") (pintype "input"))
      (node (ref "R39") (pin "1") (pinfunction "1_1") (pintype "input"))
      (node (ref "R40") (pin "1") (pinfunction "1_1") (pintype "input"))
      (node (ref "R41") (pin "2") (pinfunction "2_2") (pintype "input"))
      (node (ref "R42") (pin "2") (pinfunction "2_2") (pintype "input"))
      (node (ref "R43") (pin "2") (pinfunction "2_2") (pintype "input"))
      (node (ref "U15") (pin "4") (pinfunction "4_4") (pintype "unspecified"))
      (node (ref "U7") (pin "5") (pinfunction "VOUT_5") (pintype "unspecified"))
    )
    (net (code "3") (name "AGND") (class "Default")
      (node (ref "C24") (pin "2") (pinfunction "2_2") (pintype "input"))
      (node (ref "C25") (pin "2") (pinfunction "2_2") (pintype "input"))
      (node (ref "C26") (pin "2") (pinfunction "2_2") (pintype "unspecified"))
      (node (ref "C27") (pin "1") (pinfunction "1_1") (pintype "input"))
      (node (ref "R4") (pin "2") (pinfunction "2_2") (pintype "input"))
      (node (ref "R8") (pin "2") (pinfunction "2_2") (pintype "input"))
      (node (ref "R9") (pin "1") (pinfunction "1_1") (pintype "unspecified"))
      (node (ref "U9") (pin "17") (pinfunction "EP_17") (pintype "unspecified"))
      (node (ref "U9") (pin "2") (pinfunction "GND_2") (pintype "unspecified"))
    )
    (net (code "4") (name "BUZZER") (class "Default")
      (node (ref "R21") (pin "1") (pinfunction "1_1") (pintype "input"))
      (node (ref "U1") (pin "4") (pinfunction "4_4") (pintype "unspecified"))
    )
    (net (code "5") (name "ENCODER_DIR_L") (class "Default")
      (node (ref "H13") (pin "3") (pinfunction "3_3") (pintype "unspecified"))
      (node (ref "U1") (pin "18") (pinfunction "18_18") (pintype "unspecified"))
    )
    (net (code "6") (name "ENCODER_DIR_R") (class "Default")
      (node (ref "H14") (pin "3") (pinfunction "3_3") (pintype "unspecified"))
      (node (ref "U1") (pin "16") (pinfunction "16_16") (pintype "unspecified"))
    )
    (net (code "7") (name "ENCODER_PWM_L") (class "Default")
      (node (ref "H13") (pin "4") (pinfunction "4_4") (pintype "unspecified"))
      (node (ref "U1") (pin "22") (pinfunction "22_22") (pintype "unspecified"))
    )
    (net (code "8") (name "ENCODER_PWM_R") (class "Default")
      (node (ref "H14") (pin "4") (pinfunction "4_4") (pintype "unspecified"))
      (node (ref "U1") (pin "24") (pinfunction "24_24") (pintype "unspecified"))
    )
    (net (code "9") (name "GND") (class "Default")
      (node (ref "C10") (pin "1") (pinfunction "1_1") (pintype "unspecified"))
      (node (ref "C14") (pin "1") (pinfunction "1_1") (pintype "unspecified"))
      (node (ref "C16") (pin "2") (pinfunction "2_2") (pintype "input"))
      (node (ref "C17") (pin "2") (pinfunction "2_2") (pintype "unspecified"))
      (node (ref "C18") (pin "2") (pinfunction "2_2") (pintype "input"))
      (node (ref "C19") (pin "2") (pinfunction "2_2") (pintype "unspecified"))
      (node (ref "C21") (pin "1") (pinfunction "1_1") (pintype "unspecified"))
      (node (ref "C22") (pin "1") (pinfunction "1_1") (pintype "unspecified"))
      (node (ref "C23") (pin "1") (pinfunction "1_1") (pintype "unspecified"))
      (node (ref "C28") (pin "2") (pinfunction "2_2") (pintype "input"))
      (node (ref "C29") (pin "2") (pinfunction "2_2") (pintype "input"))
      (node (ref "C30") (pin "2") (pinfunction "2_2") (pintype "input"))
      (node (ref "CN1") (pin "1") (pinfunction "-_1") (pintype "unspecified"))
      (node (ref "CN1") (pin "3") (pinfunction "3_3") (pintype "unspecified"))
      (node (ref "CN1") (pin "4") (pinfunction "4_4") (pintype "unspecified"))
      (node (ref "FPC1") (pin "13") (pinfunction "13_13") (pintype "unspecified"))
      (node (ref "FPC1") (pin "15") (pinfunction "15_15") (pintype "unspecified"))
      (node (ref "FPC1") (pin "16") (pinfunction "16_16") (pintype "unspecified"))
      (node (ref "FPC1") (pin "2") (pinfunction "2_2") (pintype "unspecified"))
      (node (ref "FPC1") (pin "3") (pinfunction "3_3") (pintype "unspecified"))
      (node (ref "FPC1") (pin "5") (pinfunction "5_5") (pintype "unspecified"))
      (node (ref "H11") (pin "3") (pinfunction "3_3") (pintype "unspecified"))
      (node (ref "H11") (pin "4") (pinfunction "4_4") (pintype "unspecified"))
      (node (ref "H12") (pin "1") (pinfunction "1_1") (pintype "unspecified"))
      (node (ref "H12") (pin "2") (pinfunction "2_2") (pintype "unspecified"))
      (node (ref "H13") (pin "6") (pinfunction "6_6") (pintype "unspecified"))
      (node (ref "H14") (pin "6") (pinfunction "6_6") (pintype "unspecified"))
      (node (ref "LED3") (pin "1") (pinfunction "K_1") (pintype "input"))
      (node (ref "LED4") (pin "1") (pinfunction "K_1") (pintype "input"))
      (node (ref "Q3") (pin "2") (pinfunction "2_2") (pintype "input"))
      (node (ref "R22") (pin "2") (pinfunction "2_2") (pintype "input"))
      (node (ref "R27") (pin "1") (pinfunction "1_1") (pintype "input"))
      (node (ref "R33") (pin "1") (pinfunction "1_1") (pintype "input"))
      (node (ref "R34") (pin "1") (pinfunction "1_1") (pintype "input"))
      (node (ref "R37") (pin "1") (pinfunction "1_1") (pintype "input"))
      (node (ref "R9") (pin "2") (pinfunction "2_2") (pintype "unspecified"))
      (node (ref "SW1") (pin "2") (pinfunction "2_2") (pintype "unspecified"))
      (node (ref "U1") (pin "19") (pinfunction "19_19") (pintype "unspecified"))
      (node (ref "U1") (pin "2") (pinfunction "2_2") (pintype "unspecified"))
      (node (ref "U1") (pin "20") (pinfunction "20_20") (pintype "unspecified"))
      (node (ref "U1") (pin "30") (pinfunction "30_30") (pintype "unspecified"))
      (node (ref "U13") (pin "5") (pinfunction "5_5") (pintype "unspecified"))
      (node (ref "U15") (pin "3") (pinfunction "3_3") (pintype "unspecified"))
      (node (ref "U15") (pin "5") (pinfunction "5_5") (pintype "unspecified"))
      (node (ref "U15") (pin "6") (pinfunction "6_6") (pintype "unspecified"))
      (node (ref "U6") (pin "7") (pinfunction "GND_7") (pintype "unspecified"))
      (node (ref "U6") (pin "9") (pinfunction "EP_9") (pintype "unspecified"))
      (node (ref "U7") (pin "2") (pinfunction "GND_2") (pintype "unspecified"))
      (node (ref "USB1") (pin "1") (pinfunction "GND_1") (pintype "unspecified"))
      (node (ref "USB1") (pin "12") (pinfunction "GND_12") (pintype "unspecified"))
      (node (ref "USB1") (pin "13") (pinfunction "SHELL_13") (pintype "unspecified"))
      (node (ref "USB1") (pin "14") (pinfunction "SHELL_14") (pintype "unspecified"))
    )
    (net (code "10") (name "GOVERNOR") (class "Default")
      (node (ref "R25") (pin "2") (pinfunction "2_2") (pintype "input"))
      (node (ref "R26") (pin "2") (pinfunction "2_2") (pintype "input"))
      (node (ref "U1") (pin "6") (pinfunction "6_6") (pintype "unspecified"))
    )
    (net (code "11") (name "I2C_SCL") (class "Default")
      (node (ref "R13") (pin "1") (pinfunction "1_1") (pintype "input"))
      (node (ref "U1") (pin "15") (pinfunction "15_15") (pintype "unspecified"))
      (node (ref "U15") (pin "1") (pinfunction "1_1") (pintype "unspecified"))
    )
    (net (code "12") (name "I2C_SDA") (class "Default")
      (node (ref "R38") (pin "1") (pinfunction "1_1") (pintype "input"))
      (node (ref "U1") (pin "17") (pinfunction "17_17") (pintype "unspecified"))
      (node (ref "U15") (pin "2") (pinfunction "2_2") (pintype "unspecified"))
    )
    (net (code "13") (name "KEY_DOWN") (class "Default")
      (node (ref "R43") (pin "1") (pinfunction "1_1") (pintype "input"))
      (node (ref "SW1") (pin "4") (pinfunction "4_4") (pintype "unspecified"))
      (node (ref "U1") (pin "11") (pinfunction "11_11") (pintype "unspecified"))
    )
    (net (code "14") (name "KEY_LEFT") (class "Default")
      (node (ref "R40") (pin "2") (pinfunction "2_2") (pintype "input"))
      (node (ref "SW1") (pin "3") (pinfunction "3_3") (pintype "unspecified"))
      (node (ref "U1") (pin "9") (pinfunction "9_9") (pintype "unspecified"))
    )
    (net (code "15") (name "KEY_MID") (class "Default")
      (node (ref "R42") (pin "1") (pinfunction "1_1") (pintype "input"))
      (node (ref "SW1") (pin "5") (pinfunction "5_5") (pintype "unspecified"))
      (node (ref "U1") (pin "14") (pinfunction "14_14") (pintype "unspecified"))
    )
    (net (code "16") (name "KEY_RIGHT") (class "Default")
      (node (ref "R41") (pin "1") (pinfunction "1_1") (pintype "input"))
      (node (ref "SW1") (pin "6") (pinfunction "6_6") (pintype "unspecified"))
      (node (ref "U1") (pin "7") (pinfunction "7_7") (pintype "unspecified"))
    )
    (net (code "17") (name "KEY_UP") (class "Default")
      (node (ref "R39") (pin "2") (pinfunction "2_2") (pintype "input"))
      (node (ref "SW1") (pin "1") (pinfunction "1_1") (pintype "unspecified"))
      (node (ref "U1") (pin "25") (pinfunction "25_25") (pintype "unspecified"))
    )
    (net (code "18") (name "MOTOR_DIR_L") (class "Default")
      (node (ref "R12") (pin "2") (pinfunction "2_2") (pintype "input"))
      (node (ref "U1") (pin "8") (pinfunction "8_8") (pintype "unspecified"))
    )
    (net (code "19") (name "MOTOR_DIR_R") (class "Default")
      (node (ref "R11") (pin "1") (pinfunction "1_1") (pintype "input"))
      (node (ref "U1") (pin "10") (pinfunction "10_10") (pintype "unspecified"))
    )
    (net (code "20") (name "MOTOR_PWM_L") (class "Default")
      (node (ref "R18") (pin "2") (pinfunction "2_2") (pintype "input"))
      (node (ref "U1") (pin "26") (pinfunction "26_26") (pintype "unspecified"))
    )
    (net (code "21") (name "MOTOR_PWM_R") (class "Default")
      (node (ref "R17") (pin "1") (pinfunction "1_1") (pintype "input"))
      (node (ref "U1") (pin "28") (pinfunction "28_28") (pintype "unspecified"))
    )
    (net (code "22") (name "Net-(BUZZER2--)") (class "Default")
      (node (ref "BUZZER2") (pin "2") (pinfunction "-_2") (pintype "unspecified"))
      (node (ref "D3") (pin "2") (pinfunction "A_2") (pintype "unspecified"))
      (node (ref "Q3") (pin "3") (pinfunction "3_3") (pintype "input"))
    )
    (net (code "23") (name "Net-(C23-Pad2)") (class "Default")
      (node (ref "C23") (pin "2") (pinfunction "2_2") (pintype "unspecified"))
      (node (ref "R35") (pin "1") (pinfunction "1_1") (pintype "input"))
    )
    (net (code "24") (name "Net-(CN1-+)") (class "Default")
      (node (ref "CN1") (pin "2") (pinfunction "+_2") (pintype "unspecified"))
      (node (ref "D4") (pin "1") (pinfunction "K_1") (pintype "unspecified"))
      (node (ref "Q6") (pin "1") (pinfunction "S_1") (pintype "unspecified"))
      (node (ref "Q6") (pin "2") (pinfunction "S_2") (pintype "unspecified"))
      (node (ref "Q6") (pin "3") (pinfunction "S_3") (pintype "unspecified"))
      (node (ref "U8") (pin "3") (pinfunction "3_3") (pintype "unspecified"))
    )
    (net (code "25") (name "Net-(D4-A)") (class "Default")
      (node (ref "D4") (pin "2") (pinfunction "A_2") (pintype "unspecified"))
      (node (ref "R27") (pin "2") (pinfunction "2_2") (pintype "input"))
      (node (ref "U8") (pin "1") (pinfunction "1_1") (pintype "unspecified"))
    )
    (net (code "26") (name "Net-(D5-A)") (class "Default")
      (node (ref "C14") (pin "2") (pinfunction "2_2") (pintype "unspecified"))
      (node (ref "C29") (pin "1") (pinfunction "1_1") (pintype "input"))
      (node (ref "D5") (pin "1") (pinfunction "A_1") (pintype "unspecified"))
      (node (ref "L1") (pin "2") (pinfunction "2_2") (pintype "unspecified"))
    )
    (net (code "27") (name "Net-(D6-K)") (class "Default")
      (node (ref "C21") (pin "2") (pinfunction "2_2") (pintype "unspecified"))
      (node (ref "C22") (pin "2") (pinfunction "2_2") (pintype "unspecified"))
      (node (ref "C28") (pin "1") (pinfunction "1_1") (pintype "input"))
      (node (ref "D6") (pin "2") (pinfunction "K_2") (pintype "unspecified"))
      (node (ref "U6") (pin "2") (pinfunction "VIN_2") (pintype "unspecified"))
      (node (ref "U6") (pin "3") (pinfunction "EN_3") (pintype "unspecified"))
    )
    (net (code "28") (name "Net-(H11-Pad1)") (class "Default")
      (node (ref "H11") (pin "1") (pinfunction "1_1") (pintype "unspecified"))
      (node (ref "R11") (pin "2") (pinfunction "2_2") (pintype "input"))
    )
    (net (code "29") (name "Net-(H11-Pad2)") (class "Default")
      (node (ref "H11") (pin "2") (pinfunction "2_2") (pintype "unspecified"))
      (node (ref "R12") (pin "1") (pinfunction "1_1") (pintype "input"))
    )
    (net (code "30") (name "Net-(H11-Pad5)") (class "Default")
      (node (ref "H11") (pin "5") (pinfunction "5_5") (pintype "unspecified"))
      (node (ref "R17") (pin "2") (pinfunction "2_2") (pintype "input"))
    )
    (net (code "31") (name "Net-(H11-Pad6)") (class "Default")
      (node (ref "H11") (pin "6") (pinfunction "6_6") (pintype "unspecified"))
      (node (ref "R18") (pin "1") (pinfunction "1_1") (pintype "input"))
    )
    (net (code "32") (name "Net-(H12-Pad5)") (class "Default")
      (node (ref "H12") (pin "5") (pinfunction "5_5") (pintype "unspecified"))
      (node (ref "R26") (pin "1") (pinfunction "1_1") (pintype "input"))
    )
    (net (code "33") (name "Net-(H12-Pad6)") (class "Default")
      (node (ref "H12") (pin "6") (pinfunction "6_6") (pintype "unspecified"))
      (node (ref "R25") (pin "1") (pinfunction "1_1") (pintype "input"))
    )
    (net (code "34") (name "Net-(LED3-A)") (class "Default")
      (node (ref "LED3") (pin "2") (pinfunction "A_2") (pintype "input"))
      (node (ref "R29") (pin "1") (pinfunction "1_1") (pintype "input"))
    )
    (net (code "35") (name "Net-(LED4-A)") (class "Default")
      (node (ref "LED4") (pin "2") (pinfunction "A_2") (pintype "input"))
      (node (ref "R32") (pin "2") (pinfunction "2_2") (pintype "input"))
    )
    (net (code "36") (name "Net-(Q3-Pad1)") (class "Default")
      (node (ref "Q3") (pin "1") (pinfunction "1_1") (pintype "input"))
      (node (ref "R21") (pin "2") (pinfunction "2_2") (pintype "input"))
      (node (ref "R22") (pin "1") (pinfunction "1_1") (pintype "input"))
    )
    (net (code "37") (name "Net-(Q6-G)") (class "Default")
      (node (ref "Q6") (pin "4") (pinfunction "G_4") (pintype "unspecified"))
      (node (ref "R36") (pin "2") (pinfunction "2_2") (pintype "input"))
    )
    (net (code "38") (name "Net-(Q7-D)") (class "Default")
      (node (ref "Q7") (pin "3") (pinfunction "D_3") (pintype "unspecified"))
      (node (ref "Q8") (pin "3") (pinfunction "D_3") (pintype "unspecified"))
    )
    (net (code "39") (name "Net-(R30-Pad1)") (class "Default")
      (node (ref "R30") (pin "1") (pinfunction "1_1") (pintype "input"))
      (node (ref "R31") (pin "2") (pinfunction "2_2") (pintype "input"))
    )
    (net (code "40") (name "Net-(R36-Pad1)") (class "Default")
      (node (ref "R36") (pin "1") (pinfunction "1_1") (pintype "input"))
      (node (ref "U8") (pin "2") (pinfunction "2_2") (pintype "unspecified"))
    )
    (net (code "41") (name "Net-(U6-BOOT)") (class "Default")
      (node (ref "C13") (pin "2") (pinfunction "2_2") (pintype "unspecified"))
      (node (ref "U6") (pin "1") (pinfunction "BOOT_1") (pintype "unspecified"))
    )
    (net (code "42") (name "Net-(U6-COMP)") (class "Default")
      (node (ref "R35") (pin "2") (pinfunction "2_2") (pintype "input"))
      (node (ref "U6") (pin "6") (pinfunction "COMP_6") (pintype "unspecified"))
    )
    (net (code "43") (name "Net-(U6-FB)") (class "Default")
      (node (ref "R31") (pin "1") (pinfunction "1_1") (pintype "input"))
      (node (ref "R33") (pin "2") (pinfunction "2_2") (pintype "input"))
      (node (ref "U6") (pin "5") (pinfunction "FB_5") (pintype "unspecified"))
    )
    (net (code "44") (name "Net-(U6-RT{slash}CLK)") (class "Default")
      (node (ref "R34") (pin "2") (pinfunction "2_2") (pintype "input"))
      (node (ref "U6") (pin "4") (pinfunction "RT/CLK_4") (pintype "unspecified"))
    )
    (net (code "45") (name "Net-(U6-SW)") (class "Default")
      (node (ref "C13") (pin "1") (pinfunction "1_1") (pintype "unspecified"))
      (node (ref "L1") (pin "1") (pinfunction "1_1") (pintype "unspecified"))
      (node (ref "U6") (pin "8") (pinfunction "SW_8") (pintype "unspecified"))
    )
    (net (code "46") (name "Net-(U9-V3)") (class "Default")
      (node (ref "C26") (pin "1") (pinfunction "1_1") (pintype "unspecified"))
      (node (ref "U9") (pin "6") (pinfunction "V3_6") (pintype "unspecified"))
    )
    (net (code "47") (name "Net-(USB1-CC1)") (class "Default")
      (node (ref "R8") (pin "1") (pinfunction "1_1") (pintype "input"))
      (node (ref "USB1") (pin "4") (pinfunction "CC1_4") (pintype "unspecified"))
    )
    (net (code "48") (name "Net-(USB1-CC2)") (class "Default")
      (node (ref "R4") (pin "1") (pinfunction "1_1") (pintype "input"))
      (node (ref "USB1") (pin "10") (pinfunction "CC2_10") (pintype "unspecified"))
    )
    (net (code "49") (name "RX") (class "Default")
      (node (ref "U1") (pin "5") (pinfunction "5_5") (pintype "unspecified"))
      (node (ref "U13") (pin "3") (pinfunction "3_3") (pintype "unspecified"))
      (node (ref "U9") (pin "4") (pinfunction "TXD_4") (pintype "unspecified"))
    )
    (net (code "50") (name "TFFT180_SDA") (class "Default")
      (node (ref "FPC1") (pin "8") (pinfunction "8_8") (pintype "unspecified"))
      (node (ref "U1") (pin "27") (pinfunction "27_27") (pintype "unspecified"))
    )
    (net (code "51") (name "TFT180_CS") (class "Default")
      (node (ref "FPC1") (pin "12") (pinfunction "12_12") (pintype "unspecified"))
      (node (ref "U1") (pin "23") (pinfunction "23_23") (pintype "unspecified"))
    )
    (net (code "52") (name "TFT180_DC") (class "Default")
      (node (ref "FPC1") (pin "7") (pinfunction "7_7") (pintype "unspecified"))
      (node (ref "U1") (pin "12") (pinfunction "12_12") (pintype "unspecified"))
    )
    (net (code "53") (name "TFT180_RES") (class "Default")
      (node (ref "FPC1") (pin "6") (pinfunction "6_6") (pintype "unspecified"))
      (node (ref "U1") (pin "13") (pinfunction "13_13") (pintype "unspecified"))
    )
    (net (code "54") (name "TFT180_SCL") (class "Default")
      (node (ref "FPC1") (pin "9") (pinfunction "9_9") (pintype "unspecified"))
      (node (ref "U1") (pin "21") (pinfunction "21_21") (pintype "unspecified"))
    )
    (net (code "55") (name "TX") (class "Default")
      (node (ref "U1") (pin "3") (pinfunction "3_3") (pintype "unspecified"))
      (node (ref "U13") (pin "1") (pinfunction "1_1") (pintype "unspecified"))
      (node (ref "U9") (pin "5") (pinfunction "RXD_5") (pintype "unspecified"))
    )
    (net (code "56") (name "UD+") (class "Default")
      (node (ref "U9") (pin "7") (pinfunction "UD+_7") (pintype "unspecified"))
      (node (ref "USB1") (pin "6") (pinfunction "DP1_6") (pintype "unspecified"))
      (node (ref "USB1") (pin "8") (pinfunction "DP2_8") (pintype "unspecified"))
    )
    (net (code "57") (name "UD-") (class "Default")
      (node (ref "U9") (pin "8") (pinfunction "UD-_8") (pintype "unspecified"))
      (node (ref "USB1") (pin "5") (pinfunction "DN2_5") (pintype "unspecified"))
      (node (ref "USB1") (pin "7") (pinfunction "DN1_7") (pintype "unspecified"))
    )
    (net (code "58") (name "VCCBAT") (class "Default")
      (node (ref "D6") (pin "1") (pinfunction "A_1") (pintype "unspecified"))
      (node (ref "Q6") (pin "5") (pinfunction "D_5") (pintype "unspecified"))
    )
    (net (code "59") (name "VCCBAT_5V") (class "Default")
      (node (ref "D5") (pin "2") (pinfunction "K_2") (pintype "unspecified"))
      (node (ref "Q8") (pin "2") (pinfunction "S_2") (pintype "unspecified"))
      (node (ref "R30") (pin "2") (pinfunction "2_2") (pintype "input"))
    )
    (net (code "60") (name "VCCUSB") (class "Default")
      (node (ref "D2") (pin "2") (pinfunction "A_2") (pintype "unspecified"))
      (node (ref "Q7") (pin "1") (pinfunction "G_1") (pintype "unspecified"))
      (node (ref "Q8") (pin "1") (pinfunction "G_1") (pintype "unspecified"))
      (node (ref "R37") (pin "2") (pinfunction "2_2") (pintype "input"))
      (node (ref "USB1") (pin "11") (pinfunction "VBUS_11") (pintype "unspecified"))
      (node (ref "USB1") (pin "2") (pinfunction "VBUS_2") (pintype "unspecified"))
    )
    (net (code "61") (name "unconnected-(FPC1-Pad1)") (class "Default")
      (node (ref "FPC1") (pin "1") (pinfunction "1_1") (pintype "unspecified+no_connect"))
    )
    (net (code "62") (name "unconnected-(FPC1-Pad14)") (class "Default")
      (node (ref "FPC1") (pin "14") (pinfunction "14_14") (pintype "unspecified+no_connect"))
    )
    (net (code "63") (name "unconnected-(H12-Pad3)") (class "Default")
      (node (ref "H12") (pin "3") (pinfunction "3_3") (pintype "unspecified+no_connect"))
    )
    (net (code "64") (name "unconnected-(H12-Pad4)") (class "Default")
      (node (ref "H12") (pin "4") (pinfunction "4_4") (pintype "unspecified+no_connect"))
    )
    (net (code "65") (name "unconnected-(H13-Pad1)") (class "Default")
      (node (ref "H13") (pin "1") (pinfunction "1_1") (pintype "unspecified+no_connect"))
    )
    (net (code "66") (name "unconnected-(H13-Pad2)") (class "Default")
      (node (ref "H13") (pin "2") (pinfunction "2_2") (pintype "unspecified+no_connect"))
    )
    (net (code "67") (name "unconnected-(H14-Pad1)") (class "Default")
      (node (ref "H14") (pin "1") (pinfunction "1_1") (pintype "unspecified+no_connect"))
    )
    (net (code "68") (name "unconnected-(H14-Pad2)") (class "Default")
      (node (ref "H14") (pin "2") (pinfunction "2_2") (pintype "unspecified+no_connect"))
    )
    (net (code "69") (name "unconnected-(U1-Pad1)") (class "Default")
      (node (ref "U1") (pin "1") (pinfunction "1_1") (pintype "unspecified+no_connect"))
    )
    (net (code "70") (name "unconnected-(U2-Pad1)") (class "Default")
      (node (ref "U2") (pin "1") (pinfunction "1_1") (pintype "unspecified+no_connect"))
    )
    (net (code "71") (name "unconnected-(U2-Pad2)") (class "Default")
      (node (ref "U2") (pin "2") (pinfunction "2_2") (pintype "unspecified+no_connect"))
    )
    (net (code "72") (name "unconnected-(U2-Pad3)") (class "Default")
      (node (ref "U2") (pin "3") (pinfunction "3_3") (pintype "unspecified+no_connect"))
    )
    (net (code "73") (name "unconnected-(U2-Pad4)") (class "Default")
      (node (ref "U2") (pin "4") (pinfunction "4_4") (pintype "unspecified+no_connect"))
    )
    (net (code "74") (name "unconnected-(U2-Pad5)") (class "Default")
      (node (ref "U2") (pin "5") (pinfunction "5_5") (pintype "unspecified+no_connect"))
    )
    (net (code "75") (name "unconnected-(U2-Pad6)") (class "Default")
      (node (ref "U2") (pin "6") (pinfunction "6_6") (pintype "unspecified+no_connect"))
    )
    (net (code "76") (name "unconnected-(U2-Pad7)") (class "Default")
      (node (ref "U2") (pin "7") (pinfunction "7_7") (pintype "unspecified+no_connect"))
    )
    (net (code "77") (name "unconnected-(U2-Pad8)") (class "Default")
      (node (ref "U2") (pin "8") (pinfunction "8_8") (pintype "unspecified+no_connect"))
    )
    (net (code "78") (name "unconnected-(U2-Pad9)") (class "Default")
      (node (ref "U2") (pin "9") (pinfunction "9_9") (pintype "unspecified+no_connect"))
    )
    (net (code "79") (name "unconnected-(U2-Pad10)") (class "Default")
      (node (ref "U2") (pin "10") (pinfunction "10_10") (pintype "unspecified+no_connect"))
    )
    (net (code "80") (name "unconnected-(U7-NC-Pad4)") (class "Default")
      (node (ref "U7") (pin "4") (pinfunction "NC_4") (pintype "unspecified+no_connect"))
    )
    (net (code "81") (name "unconnected-(U9-ACT#-Pad10)") (class "Default")
      (node (ref "U9") (pin "10") (pinfunction "ACT#_10") (pintype "unspecified+no_connect"))
    )
    (net (code "82") (name "unconnected-(U9-CTS-Pad15)") (class "Default")
      (node (ref "U9") (pin "15") (pinfunction "CTS_15") (pintype "unspecified+no_connect"))
    )
    (net (code "83") (name "unconnected-(U9-DCD-Pad11)") (class "Default")
      (node (ref "U9") (pin "11") (pinfunction "DCD_11") (pintype "unspecified+no_connect"))
    )
    (net (code "84") (name "unconnected-(U9-DSR-Pad14)") (class "Default")
      (node (ref "U9") (pin "14") (pinfunction "DSR_14") (pintype "unspecified+no_connect"))
    )
    (net (code "85") (name "unconnected-(U9-DTRTNOW-Pad12)") (class "Default")
      (node (ref "U9") (pin "12") (pinfunction "DTRTNOW_12") (pintype "unspecified+no_connect"))
    )
    (net (code "86") (name "unconnected-(U9-RI-Pad16)") (class "Default")
      (node (ref "U9") (pin "16") (pinfunction "RI_16") (pintype "unspecified+no_connect"))
    )
    (net (code "87") (name "unconnected-(U9-RTS-Pad13)") (class "Default")
      (node (ref "U9") (pin "13") (pinfunction "RTS_13") (pintype "unspecified+no_connect"))
    )
    (net (code "88") (name "unconnected-(U13-Pad2)") (class "Default")
      (node (ref "U13") (pin "2") (pinfunction "2_2") (pintype "unspecified+no_connect"))
    )
    (net (code "89") (name "unconnected-(U13-Pad4)") (class "Default")
      (node (ref "U13") (pin "4") (pinfunction "4_4") (pintype "unspecified+no_connect"))
    )
    (net (code "90") (name "unconnected-(U13-Pad6)") (class "Default")
      (node (ref "U13") (pin "6") (pinfunction "6_6") (pintype "unspecified+no_connect"))
    )
    (net (code "91") (name "unconnected-(U13-Pad8)") (class "Default")
      (node (ref "U13") (pin "8") (pinfunction "8_8") (pintype "unspecified+no_connect"))
    )
    (net (code "92") (name "unconnected-(USB1-SBU1-Pad9)") (class "Default")
      (node (ref "USB1") (pin "9") (pinfunction "SBU1_9") (pintype "unspecified+no_connect"))
    )
    (net (code "93") (name "unconnected-(USB1-SBU2-Pad3)") (class "Default")
      (node (ref "USB1") (pin "3") (pinfunction "SBU2_3") (pintype "unspecified+no_connect"))
    )
  )
)
